# rfv1.net
KiCad netlist of a schematic drawn in EAGLE
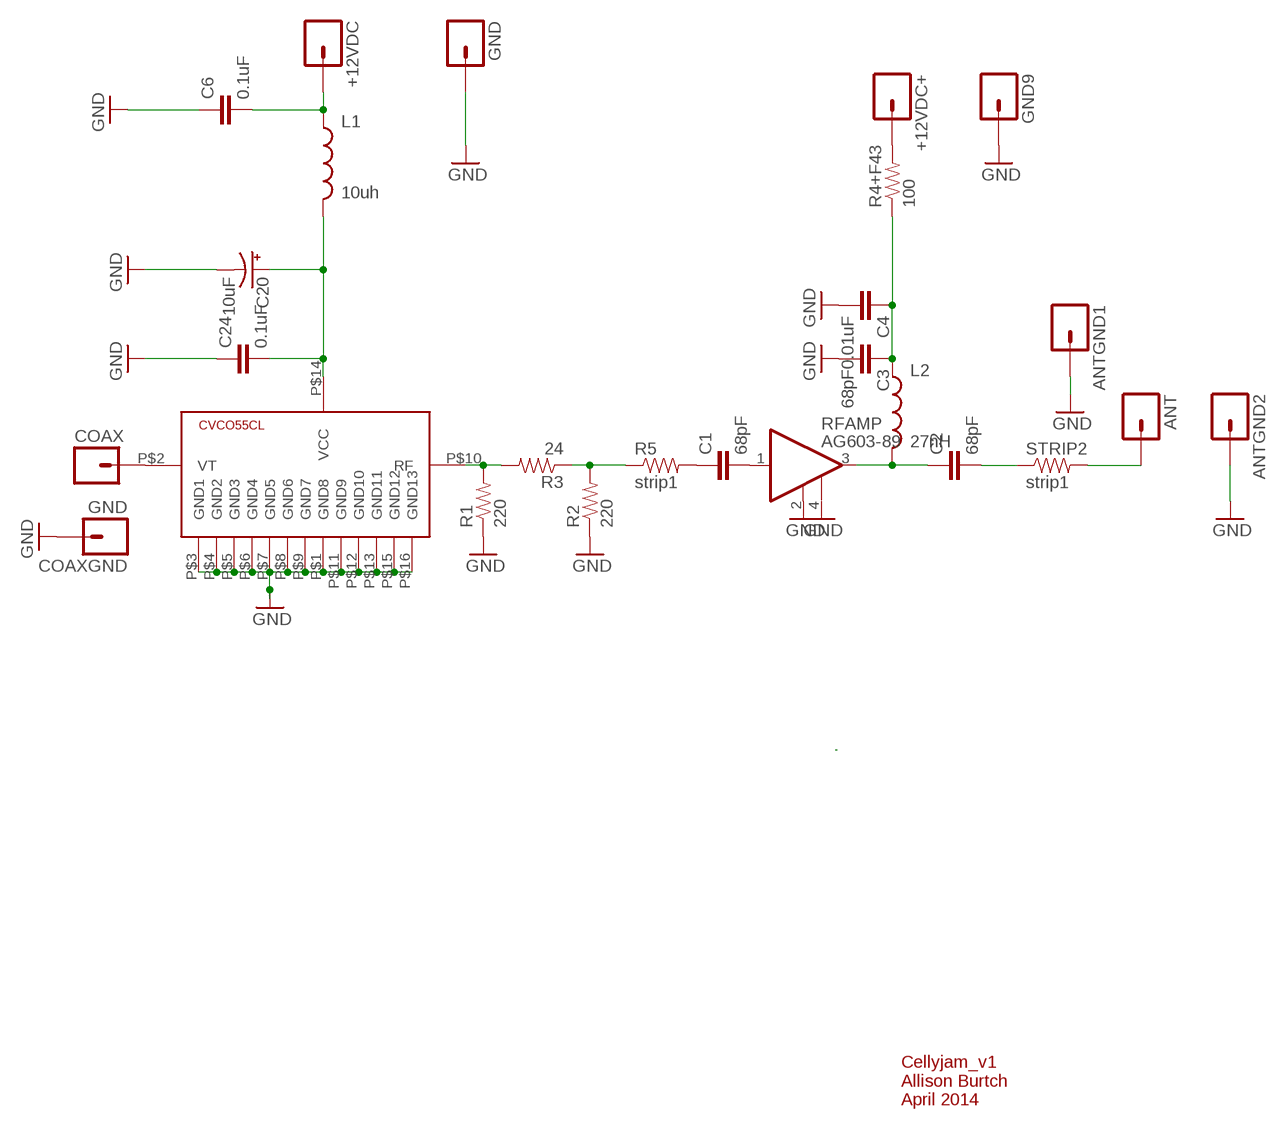
[diagram p0: schematic, sheet 1]

(export (version "E")
  (design (tool "Eeschema 10.0.6"))
  (components
    (comp (ref "+12VDC")
      (value "M01OFFSET")
      (footprint "eagle-import:1X01_OFFSET")
      (libsource (lib "eagle-import") (part "M01OFFSET"))
    )
    (comp (ref "+12VDC+")
      (value "M01OFFSET")
      (footprint "eagle-import:1X01_OFFSET")
      (libsource (lib "eagle-import") (part "M01OFFSET"))
    )
    (comp (ref "ANT")
      (value "M01OFFSET")
      (footprint "eagle-import:1X01_OFFSET")
      (libsource (lib "eagle-import") (part "M01OFFSET"))
    )
    (comp (ref "ANTGND1")
      (value "M01OFFSET")
      (footprint "eagle-import:1X01_OFFSET")
      (libsource (lib "eagle-import") (part "M01OFFSET"))
    )
    (comp (ref "ANTGND2")
      (value "M01OFFSET")
      (footprint "eagle-import:1X01_OFFSET")
      (libsource (lib "eagle-import") (part "M01OFFSET"))
    )
    (comp (ref "C1")
      (value "68pF")
      (footprint "eagle-import:0603-CAP")
      (libsource (lib "eagle-import") (part "CAP0603-CAP"))
    )
    (comp (ref "C2")
      (value "68pF")
      (footprint "eagle-import:0603-CAP")
      (libsource (lib "eagle-import") (part "CAP0603-CAP"))
    )
    (comp (ref "C3")
      (value "68pF")
      (footprint "eagle-import:0603-CAP")
      (libsource (lib "eagle-import") (part "CAP0603-CAP"))
    )
    (comp (ref "C4")
      (value "0.01uF")
      (footprint "eagle-import:0603-CAP")
      (libsource (lib "eagle-import") (part "CAP0603-CAP"))
    )
    (comp (ref "C6")
      (value "0.1uF")
      (footprint "eagle-import:0603-CAP")
      (libsource (lib "eagle-import") (part "SparkFun-Passives_CAP0603-CAP"))
    )
    (comp (ref "C20")
      (value "10uF")
      (footprint "eagle-import:PANASONIC_C")
      (libsource (lib "eagle-import") (part "CAP_POLC"))
    )
    (comp (ref "C24")
      (value "0.1uF")
      (footprint "eagle-import:0603-CAP")
      (libsource (lib "eagle-import") (part "SparkFun-Passives_CAP0603-CAP"))
    )
    (comp (ref "COAX")
      (value "M01OFFSET")
      (footprint "eagle-import:1X01_OFFSET")
      (libsource (lib "eagle-import") (part "M01OFFSET"))
    )
    (comp (ref "COAXGND")
      (value "GND")
      (footprint "eagle-import:1X01_OFFSET")
      (libsource (lib "eagle-import") (part "M01OFFSET"))
    )
    (comp (ref "GND")
      (value "M01OFFSET")
      (footprint "eagle-import:1X01_OFFSET")
      (libsource (lib "eagle-import") (part "M01OFFSET"))
    )
    (comp (ref "GND9")
      (value "M01OFFSET")
      (footprint "eagle-import:1X01_OFFSET")
      (libsource (lib "eagle-import") (part "M01OFFSET"))
    )
    (comp (ref "L1")
      (value "10uh")
      (footprint "eagle-import:0603")
      (libsource (lib "eagle-import") (part "INDUCTOR0603"))
    )
    (comp (ref "L2")
      (value "27nH")
      (footprint "eagle-import:0603")
      (libsource (lib "eagle-import") (part "INDUCTOR0603"))
    )
    (comp (ref "R1")
      (value "220")
      (footprint "eagle-import:0603-RES")
      (libsource (lib "eagle-import") (part "RESISTOR0603-RES"))
    )
    (comp (ref "R2")
      (value "220")
      (footprint "eagle-import:0603-RES")
      (libsource (lib "eagle-import") (part "RESISTOR0603-RES"))
    )
    (comp (ref "R3")
      (value "24")
      (footprint "eagle-import:0603-RES")
      (libsource (lib "eagle-import") (part "RESISTOR0603-RES"))
    )
    (comp (ref "R4+F43")
      (value "100")
      (footprint "eagle-import:AXIAL-0.3-KIT")
      (libsource (lib "eagle-import") (part "SparkFun-Resistors_RESISTORKIT"))
    )
    (comp (ref "R5")
      (value "strip1")
      (footprint "eagle-import:0603-RES")
      (libsource (lib "eagle-import") (part "1.2MOHMS-1/10W-1%(0603)"))
    )
    (comp (ref "RFAMP")
      (value "AG603-89")
      (footprint "eagle-import:SOT89")
      (libsource (lib "eagle-import") (part "GALI-3+"))
    )
    (comp (ref "STRIP2")
      (value "strip1")
      (footprint "eagle-import:0603-RES")
      (libsource (lib "eagle-import") (part "1.2MOHMS-1/10W-1%(0603)"))
    )
    (comp (ref "U$1")
      (value "CVCO55CL")
      (footprint "eagle-import:CVCO55CL")
      (libsource (lib "eagle-import") (part "CVCO55CL"))
    )
  )
  (nets
    (net (code "1") (name "GND") (class "Default")
      (node (ref "ANTGND1") (pin "1") (pinfunction "1_1") (pintype "passive"))
      (node (ref "ANTGND2") (pin "1") (pinfunction "1_1") (pintype "passive"))
      (node (ref "C20") (pin "-") (pinfunction "-_-") (pintype "passive"))
      (node (ref "C24") (pin "1") (pinfunction "1_1") (pintype "passive"))
      (node (ref "C3") (pin "2") (pinfunction "2_2") (pintype "passive"))
      (node (ref "C4") (pin "2") (pinfunction "2_2") (pintype "passive"))
      (node (ref "C6") (pin "1") (pinfunction "1_1") (pintype "passive"))
      (node (ref "COAXGND") (pin "1") (pinfunction "1_1") (pintype "passive"))
      (node (ref "GND") (pin "1") (pinfunction "1_1") (pintype "passive"))
      (node (ref "GND9") (pin "1") (pinfunction "1_1") (pintype "passive"))
      (node (ref "R1") (pin "1") (pinfunction "1_1") (pintype "passive"))
      (node (ref "R2") (pin "1") (pinfunction "1_1") (pintype "passive"))
      (node (ref "RFAMP") (pin "2") (pinfunction "GND_2") (pintype "power_in"))
      (node (ref "RFAMP") (pin "4") (pinfunction "GND_4") (pintype "power_in"))
      (node (ref "U$1") (pin "P$1") (pinfunction "GND8_P$1") (pintype "bidirectional"))
      (node (ref "U$1") (pin "P$11") (pinfunction "GND9_P$11") (pintype "bidirectional"))
      (node (ref "U$1") (pin "P$12") (pinfunction "GND10_P$12") (pintype "bidirectional"))
      (node (ref "U$1") (pin "P$13") (pinfunction "GND11_P$13") (pintype "bidirectional"))
      (node (ref "U$1") (pin "P$15") (pinfunction "GND12_P$15") (pintype "bidirectional"))
      (node (ref "U$1") (pin "P$16") (pinfunction "GND13_P$16") (pintype "bidirectional"))
      (node (ref "U$1") (pin "P$3") (pinfunction "GND1_P$3") (pintype "bidirectional"))
      (node (ref "U$1") (pin "P$4") (pinfunction "GND2_P$4") (pintype "bidirectional"))
      (node (ref "U$1") (pin "P$5") (pinfunction "GND3_P$5") (pintype "bidirectional"))
      (node (ref "U$1") (pin "P$6") (pinfunction "GND4_P$6") (pintype "bidirectional"))
      (node (ref "U$1") (pin "P$7") (pinfunction "GND5_P$7") (pintype "bidirectional"))
      (node (ref "U$1") (pin "P$8") (pinfunction "GND6_P$8") (pintype "bidirectional"))
      (node (ref "U$1") (pin "P$9") (pinfunction "GND7_P$9") (pintype "bidirectional"))
    )
    (net (code "2") (name "Net-(+12VDC-Pad1)") (class "Default")
      (node (ref "+12VDC") (pin "1") (pinfunction "1_1") (pintype "passive"))
      (node (ref "C6") (pin "2") (pinfunction "2_2") (pintype "passive"))
      (node (ref "L1") (pin "1") (pinfunction "1_1") (pintype "passive"))
    )
    (net (code "3") (name "Net-(ANT-Pad1)") (class "Default")
      (node (ref "ANT") (pin "1") (pinfunction "1_1") (pintype "passive"))
      (node (ref "STRIP2") (pin "2") (pinfunction "2_2") (pintype "passive"))
    )
    (net (code "4") (name "Net-(C1-Pad1)") (class "Default")
      (node (ref "C1") (pin "1") (pinfunction "1_1") (pintype "passive"))
      (node (ref "R5") (pin "2") (pinfunction "2_2") (pintype "passive"))
    )
    (net (code "5") (name "Net-(C2-Pad2)") (class "Default")
      (node (ref "C2") (pin "2") (pinfunction "2_2") (pintype "passive"))
      (node (ref "STRIP2") (pin "1") (pinfunction "1_1") (pintype "passive"))
    )
    (net (code "6") (name "Net-(R2-Pad2)") (class "Default")
      (node (ref "R2") (pin "2") (pinfunction "2_2") (pintype "passive"))
      (node (ref "R3") (pin "1") (pinfunction "1_1") (pintype "passive"))
      (node (ref "R5") (pin "1") (pinfunction "1_1") (pintype "passive"))
    )
    (net (code "7") (name "Net-(R4+F43-1)") (class "Default")
      (node (ref "C3") (pin "1") (pinfunction "1_1") (pintype "passive"))
      (node (ref "C4") (pin "1") (pinfunction "1_1") (pintype "passive"))
      (node (ref "L2") (pin "1") (pinfunction "1_1") (pintype "passive"))
      (node (ref "R4+F43") (pin "P$1") (pinfunction "1_P$1") (pintype "passive"))
    )
    (net (code "8") (name "Net-(R4+F43-2)") (class "Default")
      (node (ref "+12VDC+") (pin "1") (pinfunction "1_1") (pintype "passive"))
      (node (ref "R4+F43") (pin "P$2") (pinfunction "2_P$2") (pintype "passive"))
    )
    (net (code "9") (name "Net-(RFAMP-IN)") (class "Default")
      (node (ref "C1") (pin "2") (pinfunction "2_2") (pintype "passive"))
      (node (ref "RFAMP") (pin "1") (pinfunction "IN_1") (pintype "input"))
    )
    (net (code "10") (name "Net-(RFAMP-OUT)") (class "Default")
      (node (ref "C2") (pin "1") (pinfunction "1_1") (pintype "passive"))
      (node (ref "L2") (pin "2") (pinfunction "2_2") (pintype "passive"))
      (node (ref "RFAMP") (pin "3") (pinfunction "OUT_3") (pintype "output"))
    )
    (net (code "11") (name "Net-(U$1-RF)") (class "Default")
      (node (ref "R1") (pin "2") (pinfunction "2_2") (pintype "passive"))
      (node (ref "R3") (pin "2") (pinfunction "2_2") (pintype "passive"))
      (node (ref "U$1") (pin "P$10") (pinfunction "RF_P$10") (pintype "bidirectional"))
    )
    (net (code "12") (name "Net-(U$1-VCC)") (class "Default")
      (node (ref "C20") (pin "+") (pinfunction "+_+") (pintype "passive"))
      (node (ref "C24") (pin "2") (pinfunction "2_2") (pintype "passive"))
      (node (ref "L1") (pin "2") (pinfunction "2_2") (pintype "passive"))
      (node (ref "U$1") (pin "P$14") (pinfunction "VCC_P$14") (pintype "bidirectional"))
    )
    (net (code "13") (name "Net-(U$1-VT)") (class "Default")
      (node (ref "COAX") (pin "1") (pinfunction "1_1") (pintype "passive"))
      (node (ref "U$1") (pin "P$2") (pinfunction "VT_P$2") (pintype "bidirectional"))
    )
  )
)
